# power_5V.net
KiCad netlist of a schematic drawn in Altium Designer
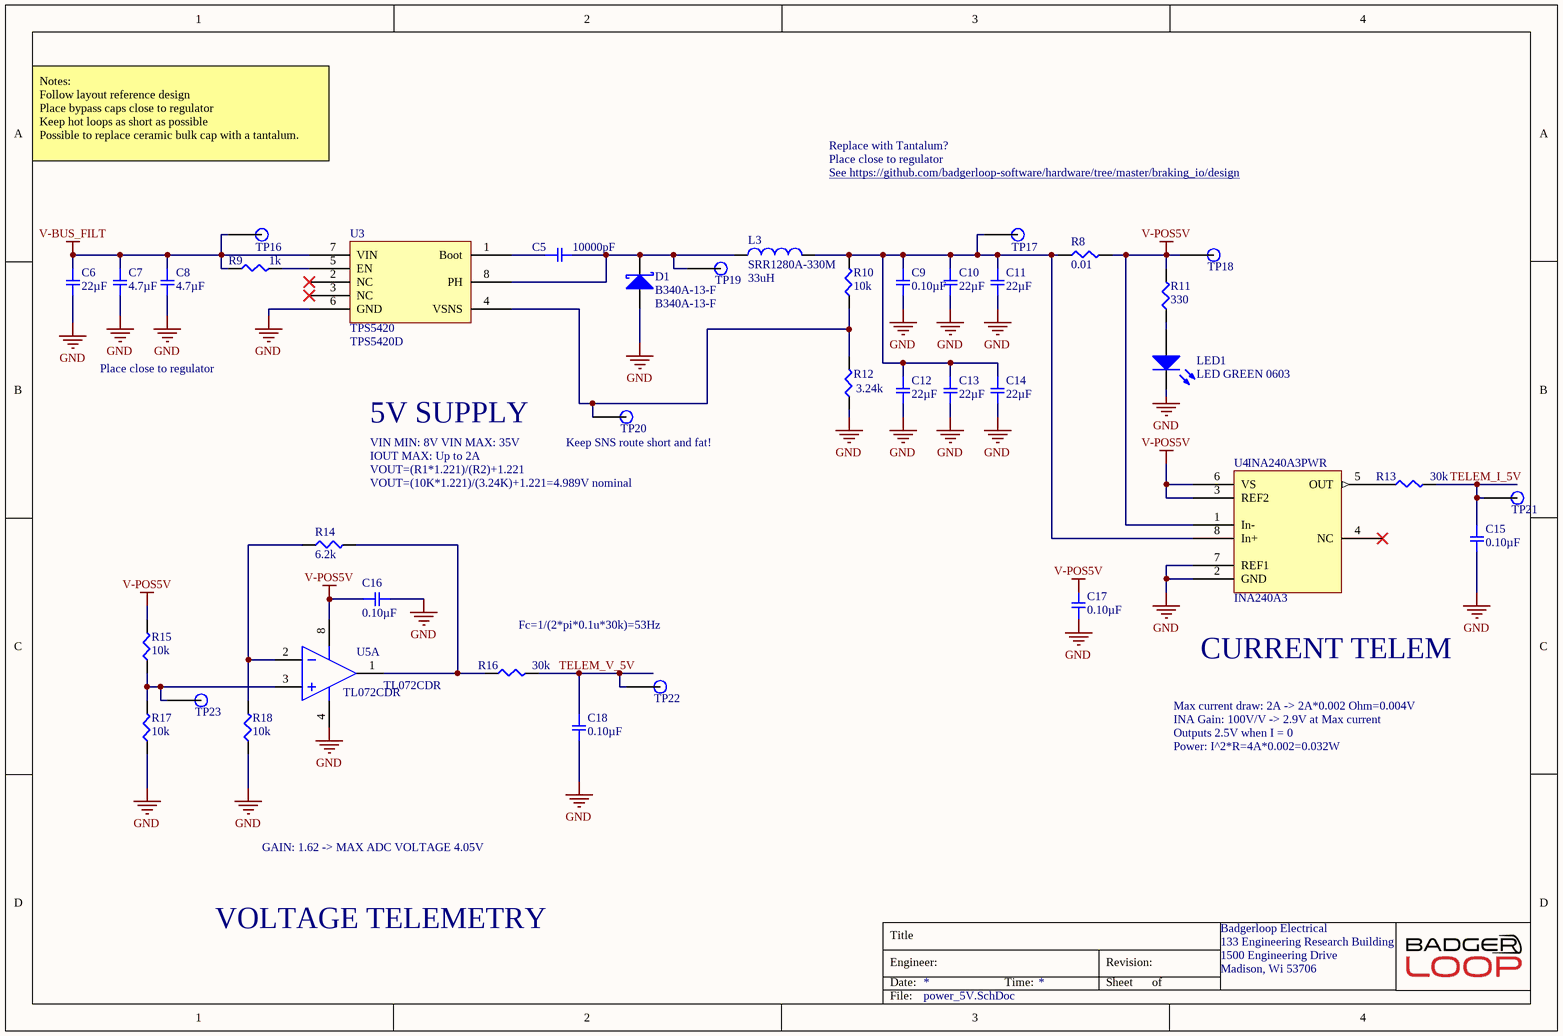
[diagram p0: power_5V.SchDoc]

(export (version "E")
  (design (tool "Eeschema 10.0.6"))
  (components
    (comp (ref "C5")
      (value "10000pF")
      (footprint "SMD-0805C")
      (description "CAP CER 10000PF 250V X7T 0805")
      (fields
        (field (name "DIGI-KEY PART NUMBER") "490-13986-1-ND")
        (field (name "PART NUMBER") "GC321AD72E103KX01D")
      )
      (libsource (lib "capacitors") (part "GC321AD72E103KX01D"))
    )
    (comp (ref "C6")
      (value "22µF")
      (footprint "SMD-1206C")
      (description "CAP CER 22UF 25V X5R 1206")
      (fields
        (field (name "DIGI-KEY PART NUMBER") "490-12451-1-ND")
        (field (name "PART NUMBER") "GRT31CR61E226ME01L")
      )
      (libsource (lib "capacitors") (part "GRT31CR61E226ME01L"))
    )
    (comp (ref "C7")
      (value "4.7µF")
      (footprint "SMD-1206C")
      (description "CAP CER 4.7UF 50V X7S 1206")
      (fields
        (field (name "DIGI-KEY PART NUMBER") "490-11167-1-ND")
        (field (name "PART NUMBER") "GCM31CC71H475KA03L")
      )
      (libsource (lib "capacitors") (part "GCM31CC71H475KA03L"))
    )
    (comp (ref "C8")
      (value "4.7µF")
      (footprint "SMD-1206C")
      (description "CAP CER 4.7UF 50V X7S 1206")
      (fields
        (field (name "DIGI-KEY PART NUMBER") "490-11167-1-ND")
        (field (name "PART NUMBER") "GCM31CC71H475KA03L")
      )
      (libsource (lib "capacitors") (part "GCM31CC71H475KA03L"))
    )
    (comp (ref "C9")
      (value "0.10µF")
      (footprint "SMD-0805C")
      (description "CAP CER 0.1UF 10V U2J 0805")
      (fields
        (field (name "DIGI-KEY PART NUMBER") "490-11592-1-ND")
        (field (name "PART NUMBER") "GRM21B7U1A104JA01L")
      )
      (libsource (lib "capacitors") (part "GRM21B7U1A104JA01L"))
    )
    (comp (ref "C10")
      (value "22µF")
      (footprint "SMD-1206C")
      (description "CAP CER 22UF 25V X5R 1206")
      (fields
        (field (name "DIGI-KEY PART NUMBER") "490-12451-1-ND")
        (field (name "PART NUMBER") "GRT31CR61E226ME01L")
      )
      (libsource (lib "capacitors") (part "GRT31CR61E226ME01L"))
    )
    (comp (ref "C11")
      (value "22µF")
      (footprint "SMD-1206C")
      (description "CAP CER 22UF 25V X5R 1206")
      (fields
        (field (name "DIGI-KEY PART NUMBER") "490-12451-1-ND")
        (field (name "PART NUMBER") "GRT31CR61E226ME01L")
      )
      (libsource (lib "capacitors") (part "GRT31CR61E226ME01L"))
    )
    (comp (ref "C12")
      (value "22µF")
      (footprint "SMD-1206C")
      (description "CAP CER 22UF 25V X5R 1206")
      (fields
        (field (name "DIGI-KEY PART NUMBER") "490-12451-1-ND")
        (field (name "PART NUMBER") "GRT31CR61E226ME01L")
      )
      (libsource (lib "capacitors") (part "GRT31CR61E226ME01L"))
    )
    (comp (ref "C13")
      (value "22µF")
      (footprint "SMD-1206C")
      (description "CAP CER 22UF 25V X5R 1206")
      (fields
        (field (name "DIGI-KEY PART NUMBER") "490-12451-1-ND")
        (field (name "PART NUMBER") "GRT31CR61E226ME01L")
      )
      (libsource (lib "capacitors") (part "GRT31CR61E226ME01L"))
    )
    (comp (ref "C14")
      (value "22µF")
      (footprint "SMD-1206C")
      (description "CAP CER 22UF 25V X5R 1206")
      (fields
        (field (name "DIGI-KEY PART NUMBER") "490-12451-1-ND")
        (field (name "PART NUMBER") "GRT31CR61E226ME01L")
      )
      (libsource (lib "capacitors") (part "GRT31CR61E226ME01L"))
    )
    (comp (ref "C15")
      (value "0.10µF")
      (footprint "SMD-0805C")
      (description "CAP CER 0.1UF 16V X7R 0805")
      (fields
        (field (name "DIGI-KEY PART NUMBER") "490-1683-1-ND")
        (field (name "PART NUMBER") "GRM219R71C104KA01D")
      )
      (libsource (lib "capacitors") (part "GRM219R71C104KA01D"))
    )
    (comp (ref "C16")
      (value "0.10µF")
      (footprint "SMD-0805C")
      (description "CAP CER 0.1UF 10V U2J 0805")
      (fields
        (field (name "DIGI-KEY PART NUMBER") "490-11592-1-ND")
        (field (name "PART NUMBER") "GRM21B7U1A104JA01L")
      )
      (libsource (lib "capacitors") (part "GRM21B7U1A104JA01L"))
    )
    (comp (ref "C17")
      (value "0.10µF")
      (footprint "SMD-0805C")
      (description "CAP CER 0.1UF 10V U2J 0805")
      (fields
        (field (name "DIGI-KEY PART NUMBER") "490-11592-1-ND")
        (field (name "PART NUMBER") "GRM21B7U1A104JA01L")
      )
      (libsource (lib "capacitors") (part "GRM21B7U1A104JA01L"))
    )
    (comp (ref "C18")
      (value "0.10µF")
      (footprint "SMD-0805C")
      (description "CAP CER 0.1UF 16V X7R 0805")
      (fields
        (field (name "DIGI-KEY PART NUMBER") "490-1683-1-ND")
        (field (name "PART NUMBER") "GRM219R71C104KA01D")
      )
      (libsource (lib "capacitors") (part "GRM219R71C104KA01D"))
    )
    (comp (ref "D1")
      (value "B340A-13-F")
      (footprint "DIOM4326X20N")
      (description "DIODE SCHOTTKY 40V 3A SMA")
      (fields
        (field (name "MANUFACTURER") "Diodes")
        (field (name "VOLTAGE") "40V")
        (field (name "MANUFACTURER PART NUMBER") "B340A-13-F")
      )
      (libsource (lib "misc") (part "B340A-13-F"))
    )
    (comp (ref "L3")
      (value "SRR1280A-330M")
      (footprint "INDM120125X75N")
      (description "Inductor Power Shielded Wirewound 33uH 20% 1KHz 28Q-Factor Ferrite 3.5A 57mOhm DCR Automotive T/R")
      (fields
        (field (name "MANUFACTURER") "Bourns")
        (field (name "TOLERANCE") "20%")
        (field (name "INDUCTANCE") "33uH")
      )
      (libsource (lib "misc") (part "SRR1280A-330M"))
    )
    (comp (ref "LED1")
      (value "LED GREEN 0603")
      (footprint "LED 0603 GREEN")
      (fields (field (name "MANUFACTURER") "Lite-On Inc."))
      (libsource (lib "misc") (part "LED GREEN 0603"))
    )
    (comp (ref "R8")
      (value "0.01")
      (footprint "SMD-1206-RES")
      (description "RES SMD 0.01 OHM 1% 1W 1206")
      (fields
        (field (name "PART NUMBER") "ERJ-8BWFR010V")
        (field (name "DIGI-KEY PART NUMBER") "P.010AUCT-ND")
      )
      (libsource (lib "resistors") (part "ERJ-8BWFR010V"))
    )
    (comp (ref "R9")
      (value "1k")
      (footprint "SMD-0805-RES")
      (description "RES SMD 1K OHM 5% 1/2W 0805")
      (fields
        (field (name "PART NUMBER") "ERJ-P06J102V")
        (field (name "DIGI-KEY PART NUMBER") "P1.0KADCT-ND")
      )
      (libsource (lib "resistors") (part "ERJ-P06J102V"))
    )
    (comp (ref "R10")
      (value "10k")
      (footprint "SMD-0805-RES")
      (description "RES SMD 10K OHM 5% 1/2W 0805")
      (fields (field (name "PART NUMBER") "ERJ-P06J103V") (field (name "DIGI-KEY PART NUMBER") "P10KADCT-ND"))
      (libsource (lib "resistors") (part "ERJ-P06J103V"))
    )
    (comp (ref "R11")
      (value "330")
      (footprint "SMD-0805-RES")
      (description "RES SMD 330 OHM 5% 1/2W 0805")
      (fields (field (name "PART NUMBER") "ERJ-P06J331V") (field (name "DIGI-KEY PART NUMBER") "P330ADCT-ND"))
      (libsource (lib "resistors") (part "ERJ-P06J331V"))
    )
    (comp (ref "R12")
      (value "3.24k")
      (footprint "SMD-0805-RES")
      (description "RES SMD 3.24K OHM 1% 1/8W 0805")
      (fields
        (field (name "PART NUMBER") "ERJ-6ENF3241V")
        (field (name "DIGI-KEY PART NUMBER") "P3.24KCCT-ND")
      )
      (libsource (lib "resistors") (part "ERJ-6ENF3241V"))
    )
    (comp (ref "R13")
      (value "30k")
      (footprint "SMD-0805-RES")
      (description "RES SMD 30K OHM 1% 1/8W 0805")
      (fields
        (field (name "PART NUMBER") "ERJ-6ENF3002V")
        (field (name "DIGI-KEY PART NUMBER") "P30.0KCCT-ND")
      )
      (libsource (lib "resistors") (part "ERJ-6ENF3002V"))
    )
    (comp (ref "R14")
      (value "6.2k")
      (footprint "SMD-0805-RES")
      (description "RES SMD 6.2K OHM 5% 1/2W 0805")
      (fields
        (field (name "PART NUMBER") "ERJ-P06J622V")
        (field (name "DIGI-KEY PART NUMBER") "P6.2KADCT-ND")
      )
      (libsource (lib "resistors") (part "ERJ-P06J622V"))
    )
    (comp (ref "R15")
      (value "10k")
      (footprint "SMD-0805-RES")
      (description "RES SMD 10K OHM 5% 1/2W 0805")
      (fields (field (name "PART NUMBER") "ERJ-P06J103V") (field (name "DIGI-KEY PART NUMBER") "P10KADCT-ND"))
      (libsource (lib "resistors") (part "ERJ-P06J103V"))
    )
    (comp (ref "R16")
      (value "30k")
      (footprint "SMD-0805-RES")
      (description "RES SMD 30K OHM 1% 1/8W 0805")
      (fields
        (field (name "PART NUMBER") "ERJ-6ENF3002V")
        (field (name "DIGI-KEY PART NUMBER") "P30.0KCCT-ND")
      )
      (libsource (lib "resistors") (part "ERJ-6ENF3002V"))
    )
    (comp (ref "R17")
      (value "10k")
      (footprint "SMD-0805-RES")
      (description "RES SMD 10K OHM 5% 1/2W 0805")
      (fields (field (name "PART NUMBER") "ERJ-P06J103V") (field (name "DIGI-KEY PART NUMBER") "P10KADCT-ND"))
      (libsource (lib "resistors") (part "ERJ-P06J103V"))
    )
    (comp (ref "R18")
      (value "10k")
      (footprint "SMD-0805-RES")
      (description "RES SMD 10K OHM 5% 1/2W 0805")
      (fields (field (name "PART NUMBER") "ERJ-P06J103V") (field (name "DIGI-KEY PART NUMBER") "P10KADCT-ND"))
      (libsource (lib "resistors") (part "ERJ-P06J103V"))
    )
    (comp (ref "TP16")
      (value "TP")
      (footprint "Test Point")
      (description "SMD TEST POINT")
      (libsource (lib "misc") (part "TP"))
    )
    (comp (ref "TP17")
      (value "TP")
      (footprint "Test Point")
      (description "SMD TEST POINT")
      (libsource (lib "misc") (part "TP"))
    )
    (comp (ref "TP18")
      (value "TP")
      (footprint "Test Point")
      (description "SMD TEST POINT")
      (libsource (lib "misc") (part "TP"))
    )
    (comp (ref "TP19")
      (value "TP")
      (footprint "Test Point")
      (description "SMD TEST POINT")
      (libsource (lib "misc") (part "TP"))
    )
    (comp (ref "TP20")
      (value "TP")
      (footprint "Test Point")
      (description "SMD TEST POINT")
      (libsource (lib "misc") (part "TP"))
    )
    (comp (ref "TP21")
      (value "TP")
      (footprint "Test Point")
      (description "SMD TEST POINT")
      (libsource (lib "misc") (part "TP"))
    )
    (comp (ref "TP22")
      (value "TP")
      (footprint "Test Point")
      (description "SMD TEST POINT")
      (libsource (lib "misc") (part "TP"))
    )
    (comp (ref "TP23")
      (value "TP")
      (footprint "Test Point")
      (description "SMD TEST POINT")
      (libsource (lib "misc") (part "TP"))
    )
    (comp (ref "U3")
      (value "TPS5420")
      (footprint "SOP127P600X175-8N")
      (description "5.5V to 36V Input, 2A, 500kHz Step-Down Converter")
      (fields
        (field (name "MANUFACTURER") "Texas Instruments")
        (field (name "MANUFACTURER PART NUMBER") "TPS5420D")
      )
      (libsource (lib "ic") (part "TPS5420"))
    )
    (comp (ref "U4")
      (value "INA240A3")
      (footprint "SOIC127P600X175-8N")
      (description "IC AMP CURRENT SENSE 8-TSSOP 100V/V")
      (fields
        (field (name "MANUFACTURER") "Texas Instruments")
        (field (name "MANUFACTURER PART NUMBER") "INA240A3PWR")
      )
      (libsource (lib "ic") (part "INA240A3"))
    )
    (comp (ref "U5")
      (value "TL072CDR")
      (footprint "SOP127P600X175-8N")
      (description "IC OPAMP JFET 3MHZ 8SOIC")
      (fields
        (field (name "MANUFACTURER") "Texas Instruments")
        (field (name "MANUFACTURER PART NUMBER") "TL072CDR")
      )
      (libsource (lib "ic") (part "TL072CDR"))
    )
  )
  (nets
    (net (code "1") (name "/TELEM_I_5V") (class "Default")
      (node (ref "C15") (pin "1") (pinfunction "1_1") (pintype "passive"))
      (node (ref "R13") (pin "2") (pinfunction "2_2") (pintype "passive"))
      (node (ref "TP21") (pin "1") (pinfunction "1_1") (pintype "passive"))
    )
    (net (code "2") (name "/TELEM_V_5V") (class "Default")
      (node (ref "C18") (pin "1") (pinfunction "1_1") (pintype "passive"))
      (node (ref "R16") (pin "2") (pinfunction "2_2") (pintype "passive"))
      (node (ref "TP22") (pin "1") (pinfunction "1_1") (pintype "passive"))
    )
    (net (code "3") (name "GND") (class "Default")
      (node (ref "C10") (pin "2") (pinfunction "2_2") (pintype "passive"))
      (node (ref "C11") (pin "2") (pinfunction "2_2") (pintype "passive"))
      (node (ref "C12") (pin "2") (pinfunction "2_2") (pintype "passive"))
      (node (ref "C13") (pin "2") (pinfunction "2_2") (pintype "passive"))
      (node (ref "C14") (pin "2") (pinfunction "2_2") (pintype "passive"))
      (node (ref "C15") (pin "2") (pinfunction "2_2") (pintype "passive"))
      (node (ref "C16") (pin "2") (pinfunction "2_2") (pintype "passive"))
      (node (ref "C17") (pin "1") (pinfunction "1_1") (pintype "passive"))
      (node (ref "C18") (pin "2") (pinfunction "2_2") (pintype "passive"))
      (node (ref "C6") (pin "2") (pinfunction "2_2") (pintype "passive"))
      (node (ref "C7") (pin "2") (pinfunction "2_2") (pintype "passive"))
      (node (ref "C8") (pin "2") (pinfunction "2_2") (pintype "passive"))
      (node (ref "C9") (pin "2") (pinfunction "2_2") (pintype "passive"))
      (node (ref "D1") (pin "1") (pinfunction "A_1") (pintype "passive"))
      (node (ref "LED1") (pin "2") (pinfunction "K_2") (pintype "passive"))
      (node (ref "R12") (pin "1") (pinfunction "1_1") (pintype "passive"))
      (node (ref "R17") (pin "1") (pinfunction "1_1") (pintype "passive"))
      (node (ref "R18") (pin "1") (pinfunction "1_1") (pintype "passive"))
      (node (ref "U3") (pin "6") (pinfunction "GND_6") (pintype "passive"))
      (node (ref "U4") (pin "2") (pinfunction "GND_2") (pintype "power_in"))
      (node (ref "U4") (pin "7") (pinfunction "REF1_7") (pintype "passive"))
      (node (ref "U5") (pin "4") (pinfunction "V-_4") (pintype "power_in"))
    )
    (net (code "4") (name "Net-(D1-K)") (class "Default")
      (node (ref "C5") (pin "2") (pinfunction "2_2") (pintype "passive"))
      (node (ref "D1") (pin "2") (pinfunction "K_2") (pintype "passive"))
      (node (ref "L3") (pin "1") (pinfunction "1_1") (pintype "passive"))
      (node (ref "TP19") (pin "1") (pinfunction "1_1") (pintype "passive"))
      (node (ref "U3") (pin "8") (pinfunction "PH_8") (pintype "passive"))
    )
    (net (code "5") (name "Net-(LED1-A)") (class "Default")
      (node (ref "LED1") (pin "1") (pinfunction "A_1") (pintype "passive"))
      (node (ref "R11") (pin "1") (pinfunction "1_1") (pintype "passive"))
    )
    (net (code "6") (name "Net-(U3-Boot)") (class "Default")
      (node (ref "C5") (pin "1") (pinfunction "1_1") (pintype "passive"))
      (node (ref "U3") (pin "1") (pinfunction "Boot_1") (pintype "passive"))
    )
    (net (code "7") (name "Net-(U3-EN)") (class "Default")
      (node (ref "R9") (pin "2") (pinfunction "2_2") (pintype "passive"))
      (node (ref "U3") (pin "5") (pinfunction "EN_5") (pintype "passive"))
    )
    (net (code "8") (name "Net-(U3-VSNS)") (class "Default")
      (node (ref "R10") (pin "1") (pinfunction "1_1") (pintype "passive"))
      (node (ref "R12") (pin "2") (pinfunction "2_2") (pintype "passive"))
      (node (ref "TP20") (pin "1") (pinfunction "1_1") (pintype "passive"))
      (node (ref "U3") (pin "4") (pinfunction "VSNS_4") (pintype "power_in"))
    )
    (net (code "9") (name "Net-(U4-In+)") (class "Default")
      (node (ref "C10") (pin "1") (pinfunction "1_1") (pintype "passive"))
      (node (ref "C11") (pin "1") (pinfunction "1_1") (pintype "passive"))
      (node (ref "C12") (pin "1") (pinfunction "1_1") (pintype "passive"))
      (node (ref "C13") (pin "1") (pinfunction "1_1") (pintype "passive"))
      (node (ref "C14") (pin "1") (pinfunction "1_1") (pintype "passive"))
      (node (ref "C9") (pin "1") (pinfunction "1_1") (pintype "passive"))
      (node (ref "L3") (pin "2") (pinfunction "2_2") (pintype "passive"))
      (node (ref "R10") (pin "2") (pinfunction "2_2") (pintype "passive"))
      (node (ref "R8") (pin "1") (pinfunction "1_1") (pintype "passive"))
      (node (ref "TP17") (pin "1") (pinfunction "1_1") (pintype "passive"))
      (node (ref "U4") (pin "8") (pinfunction "In+_8") (pintype "passive"))
    )
    (net (code "10") (name "Net-(U4-OUT)") (class "Default")
      (node (ref "R13") (pin "1") (pinfunction "1_1") (pintype "passive"))
      (node (ref "U4") (pin "5") (pinfunction "OUT_5") (pintype "output"))
    )
    (net (code "11") (name "Net-(U5A-IN+)") (class "Default")
      (node (ref "R15") (pin "1") (pinfunction "1_1") (pintype "passive"))
      (node (ref "R17") (pin "2") (pinfunction "2_2") (pintype "passive"))
      (node (ref "TP23") (pin "1") (pinfunction "1_1") (pintype "passive"))
      (node (ref "U5") (pin "3") (pinfunction "IN+_3") (pintype "passive"))
    )
    (net (code "12") (name "Net-(U5A-IN-)") (class "Default")
      (node (ref "R14") (pin "1") (pinfunction "1_1") (pintype "passive"))
      (node (ref "R18") (pin "2") (pinfunction "2_2") (pintype "passive"))
      (node (ref "U5") (pin "2") (pinfunction "IN-_2") (pintype "passive"))
    )
    (net (code "13") (name "Net-(U5A-OUT)") (class "Default")
      (node (ref "R14") (pin "2") (pinfunction "2_2") (pintype "passive"))
      (node (ref "R16") (pin "1") (pinfunction "1_1") (pintype "passive"))
      (node (ref "U5") (pin "1") (pinfunction "OUT_1") (pintype "passive"))
    )
    (net (code "14") (name "V-BUS_FILT") (class "Default")
      (node (ref "C6") (pin "1") (pinfunction "1_1") (pintype "passive"))
      (node (ref "C7") (pin "1") (pinfunction "1_1") (pintype "passive"))
      (node (ref "C8") (pin "1") (pinfunction "1_1") (pintype "passive"))
      (node (ref "R9") (pin "1") (pinfunction "1_1") (pintype "passive"))
      (node (ref "TP16") (pin "1") (pinfunction "1_1") (pintype "passive"))
      (node (ref "U3") (pin "7") (pinfunction "VIN_7") (pintype "passive"))
    )
    (net (code "15") (name "V-POS5V") (class "Default")
      (node (ref "C16") (pin "1") (pinfunction "1_1") (pintype "passive"))
      (node (ref "C17") (pin "2") (pinfunction "2_2") (pintype "passive"))
      (node (ref "R11") (pin "2") (pinfunction "2_2") (pintype "passive"))
      (node (ref "R15") (pin "2") (pinfunction "2_2") (pintype "passive"))
      (node (ref "R8") (pin "2") (pinfunction "2_2") (pintype "passive"))
      (node (ref "TP18") (pin "1") (pinfunction "1_1") (pintype "passive"))
      (node (ref "U4") (pin "1") (pinfunction "In-_1") (pintype "passive"))
      (node (ref "U4") (pin "3") (pinfunction "REF2_3") (pintype "passive"))
      (node (ref "U4") (pin "6") (pinfunction "VS_6") (pintype "power_in"))
      (node (ref "U5") (pin "8") (pinfunction "V+_8") (pintype "power_in"))
    )
    (net (code "16") (name "unconnected-(U3-NC-Pad2)") (class "Default")
      (node (ref "U3") (pin "2") (pinfunction "NC_2") (pintype "power_in+no_connect"))
    )
    (net (code "17") (name "unconnected-(U3-NC-Pad3)") (class "Default")
      (node (ref "U3") (pin "3") (pinfunction "NC_3") (pintype "passive+no_connect"))
    )
    (net (code "18") (name "unconnected-(U4-NC-Pad4)") (class "Default")
      (node (ref "U4") (pin "4") (pinfunction "NC_4") (pintype "passive+no_connect"))
    )
  )
)
